# esp8266.net
KiCad netlist of a schematic drawn in EAGLE
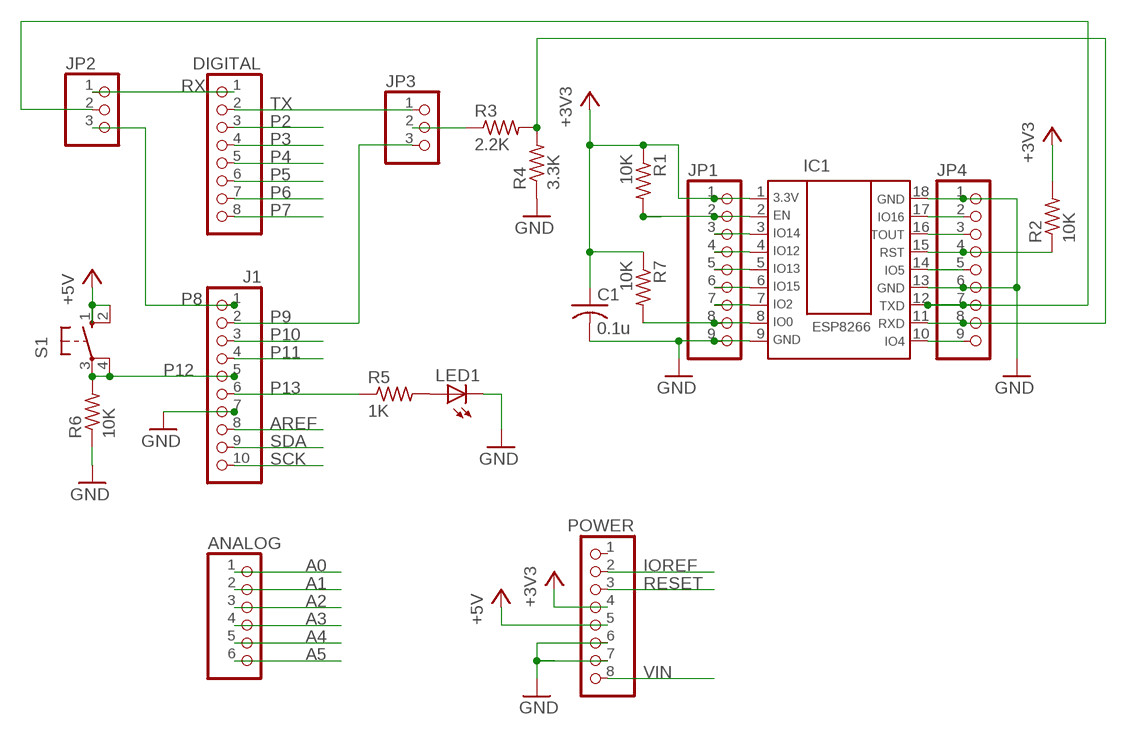
[diagram p0: schematic, sheet 1]

(export (version "E")
  (design (tool "Eeschema 10.0.6"))
  (components
    (comp (ref "ANALOG")
      (value "PINHD-1X6")
      (footprint "eagle-import:1X06")
      (libsource (lib "eagle-import") (part "PINHD-1X6"))
    )
    (comp (ref "C1")
      (value "0.1u")
      (footprint "eagle-import:C050-025X075")
      (libsource (lib "eagle-import") (part "C-US050-025X075"))
    )
    (comp (ref "DIGITAL")
      (value "PINHD-1X8TH")
      (footprint "eagle-import:1X08-TH")
      (libsource (lib "eagle-import") (part "PINHD-1X8TH"))
    )
    (comp (ref "IC1")
      (value "ESP8266")
      (footprint "eagle-import:CEREVO-PKG")
      (libsource (lib "eagle-import") (part "ESP8266"))
    )
    (comp (ref "J1")
      (value "PINHD-1X10TH")
      (footprint "eagle-import:1X10-TH")
      (libsource (lib "eagle-import") (part "PINHD-1X10TH"))
    )
    (comp (ref "JP1")
      (value "PINHD-1X9")
      (footprint "eagle-import:1X09")
      (libsource (lib "eagle-import") (part "PINHD-1X9"))
    )
    (comp (ref "JP2")
      (value "PINHD-1X3")
      (footprint "eagle-import:1X03")
      (libsource (lib "eagle-import") (part "PINHD-1X3"))
    )
    (comp (ref "JP3")
      (value "PINHD-1X3")
      (footprint "eagle-import:1X03")
      (libsource (lib "eagle-import") (part "PINHD-1X3"))
    )
    (comp (ref "JP4")
      (value "PINHD-1X9")
      (footprint "eagle-import:1X09")
      (libsource (lib "eagle-import") (part "PINHD-1X9"))
    )
    (comp (ref "LED1")
      (value "LED3MM")
      (footprint "eagle-import:LED3MM")
      (libsource (lib "eagle-import") (part "LED3MM"))
    )
    (comp (ref "POWER")
      (value "PINHD-1X8TH")
      (footprint "eagle-import:1X08-TH")
      (libsource (lib "eagle-import") (part "PINHD-1X8TH"))
    )
    (comp (ref "R1")
      (value "10K")
      (footprint "eagle-import:0207_10")
      (libsource (lib "eagle-import") (part "R-US_0207/10"))
    )
    (comp (ref "R2")
      (value "10K")
      (footprint "eagle-import:0207_10")
      (libsource (lib "eagle-import") (part "R-US_0207/10"))
    )
    (comp (ref "R3")
      (value "2.2K")
      (footprint "eagle-import:0207_10")
      (libsource (lib "eagle-import") (part "R-US_0207/10"))
    )
    (comp (ref "R4")
      (value "3.3K")
      (footprint "eagle-import:0207_10")
      (libsource (lib "eagle-import") (part "R-US_0207/10"))
    )
    (comp (ref "R5")
      (value "1K")
      (footprint "eagle-import:0207_10")
      (libsource (lib "eagle-import") (part "R-US_0207/10"))
    )
    (comp (ref "R6")
      (value "10K")
      (footprint "eagle-import:0207_10")
      (libsource (lib "eagle-import") (part "R-US_0207/10"))
    )
    (comp (ref "R7")
      (value "10K")
      (footprint "eagle-import:0207_10")
      (libsource (lib "eagle-import") (part "R-US_0207/10"))
    )
    (comp (ref "S1")
      (value "10-XX")
      (footprint "eagle-import:B3F-10XX")
      (fields (field (name "MPN") "B3F-1000"))
      (libsource (lib "eagle-import") (part "10-XX"))
    )
  )
  (nets
    (net (code "1") (name "+3V3") (class "Default")
      (node (ref "C1") (pin "1") (pinfunction "1_1") (pintype "passive"))
      (node (ref "IC1") (pin "1") (pinfunction "1_1") (pintype "passive"))
      (node (ref "JP1") (pin "1") (pinfunction "1_1") (pintype "passive"))
      (node (ref "POWER") (pin "4") (pinfunction "4_4") (pintype "passive"))
      (node (ref "R1") (pin "1") (pinfunction "1_1") (pintype "passive"))
      (node (ref "R2") (pin "2") (pinfunction "2_2") (pintype "passive"))
      (node (ref "R7") (pin "1") (pinfunction "1_1") (pintype "passive"))
    )
    (net (code "2") (name "+5V") (class "Default")
      (node (ref "POWER") (pin "5") (pinfunction "5_5") (pintype "passive"))
      (node (ref "S1") (pin "1") (pinfunction "S_1") (pintype "passive"))
      (node (ref "S1") (pin "2") (pinfunction "S1_2") (pintype "passive"))
    )
    (net (code "3") (name "/A0") (class "Default")
      (node (ref "ANALOG") (pin "1") (pinfunction "1_1") (pintype "passive"))
    )
    (net (code "4") (name "/A1") (class "Default")
      (node (ref "ANALOG") (pin "2") (pinfunction "2_2") (pintype "passive"))
    )
    (net (code "5") (name "/A2") (class "Default")
      (node (ref "ANALOG") (pin "3") (pinfunction "3_3") (pintype "passive"))
    )
    (net (code "6") (name "/A3") (class "Default")
      (node (ref "ANALOG") (pin "4") (pinfunction "4_4") (pintype "passive"))
    )
    (net (code "7") (name "/A4") (class "Default")
      (node (ref "ANALOG") (pin "5") (pinfunction "5_5") (pintype "passive"))
    )
    (net (code "8") (name "/A5") (class "Default")
      (node (ref "ANALOG") (pin "6") (pinfunction "6_6") (pintype "passive"))
    )
    (net (code "9") (name "/AREF") (class "Default")
      (node (ref "J1") (pin "8") (pinfunction "8_8") (pintype "passive"))
    )
    (net (code "10") (name "/IOREF") (class "Default")
      (node (ref "POWER") (pin "2") (pinfunction "2_2") (pintype "passive"))
    )
    (net (code "11") (name "/P2") (class "Default")
      (node (ref "DIGITAL") (pin "3") (pinfunction "3_3") (pintype "passive"))
    )
    (net (code "12") (name "/P3") (class "Default")
      (node (ref "DIGITAL") (pin "4") (pinfunction "4_4") (pintype "passive"))
    )
    (net (code "13") (name "/P4") (class "Default")
      (node (ref "DIGITAL") (pin "5") (pinfunction "5_5") (pintype "passive"))
    )
    (net (code "14") (name "/P5") (class "Default")
      (node (ref "DIGITAL") (pin "6") (pinfunction "6_6") (pintype "passive"))
    )
    (net (code "15") (name "/P6") (class "Default")
      (node (ref "DIGITAL") (pin "7") (pinfunction "7_7") (pintype "passive"))
    )
    (net (code "16") (name "/P7") (class "Default")
      (node (ref "DIGITAL") (pin "8") (pinfunction "8_8") (pintype "passive"))
    )
    (net (code "17") (name "/P8") (class "Default")
      (node (ref "J1") (pin "1") (pinfunction "1_1") (pintype "passive"))
      (node (ref "JP2") (pin "3") (pinfunction "3_3") (pintype "passive"))
    )
    (net (code "18") (name "/P9") (class "Default")
      (node (ref "J1") (pin "2") (pinfunction "2_2") (pintype "passive"))
      (node (ref "JP3") (pin "3") (pinfunction "3_3") (pintype "passive"))
    )
    (net (code "19") (name "/P10") (class "Default")
      (node (ref "J1") (pin "3") (pinfunction "3_3") (pintype "passive"))
    )
    (net (code "20") (name "/P11") (class "Default")
      (node (ref "J1") (pin "4") (pinfunction "4_4") (pintype "passive"))
    )
    (net (code "21") (name "/P12") (class "Default")
      (node (ref "J1") (pin "5") (pinfunction "5_5") (pintype "passive"))
      (node (ref "R6") (pin "2") (pinfunction "2_2") (pintype "passive"))
      (node (ref "S1") (pin "3") (pinfunction "P_3") (pintype "passive"))
      (node (ref "S1") (pin "4") (pinfunction "P1_4") (pintype "passive"))
    )
    (net (code "22") (name "/P13") (class "Default")
      (node (ref "J1") (pin "6") (pinfunction "6_6") (pintype "passive"))
      (node (ref "R5") (pin "1") (pinfunction "1_1") (pintype "passive"))
    )
    (net (code "23") (name "/RESET") (class "Default")
      (node (ref "POWER") (pin "3") (pinfunction "3_3") (pintype "passive"))
    )
    (net (code "24") (name "/RX") (class "Default")
      (node (ref "DIGITAL") (pin "1") (pinfunction "1_1") (pintype "passive"))
      (node (ref "JP2") (pin "1") (pinfunction "1_1") (pintype "passive"))
    )
    (net (code "25") (name "/SCK") (class "Default")
      (node (ref "J1") (pin "10") (pinfunction "10_10") (pintype "passive"))
    )
    (net (code "26") (name "/SDA") (class "Default")
      (node (ref "J1") (pin "9") (pinfunction "9_9") (pintype "passive"))
    )
    (net (code "27") (name "/TX") (class "Default")
      (node (ref "DIGITAL") (pin "2") (pinfunction "2_2") (pintype "passive"))
      (node (ref "JP3") (pin "1") (pinfunction "1_1") (pintype "passive"))
    )
    (net (code "28") (name "/VIN") (class "Default")
      (node (ref "POWER") (pin "8") (pinfunction "8_8") (pintype "passive"))
    )
    (net (code "29") (name "GND") (class "Default")
      (node (ref "C1") (pin "2") (pinfunction "2_2") (pintype "passive"))
      (node (ref "IC1") (pin "13") (pinfunction "13_13") (pintype "passive"))
      (node (ref "IC1") (pin "18") (pinfunction "18_18") (pintype "passive"))
      (node (ref "IC1") (pin "9") (pinfunction "9_9") (pintype "passive"))
      (node (ref "J1") (pin "7") (pinfunction "7_7") (pintype "passive"))
      (node (ref "JP1") (pin "9") (pinfunction "9_9") (pintype "passive"))
      (node (ref "JP4") (pin "1") (pinfunction "1_1") (pintype "passive"))
      (node (ref "JP4") (pin "6") (pinfunction "6_6") (pintype "passive"))
      (node (ref "LED1") (pin "K") (pinfunction "C_K") (pintype "passive"))
      (node (ref "POWER") (pin "6") (pinfunction "6_6") (pintype "passive"))
      (node (ref "POWER") (pin "7") (pinfunction "7_7") (pintype "passive"))
      (node (ref "R4") (pin "1") (pinfunction "1_1") (pintype "passive"))
      (node (ref "R6") (pin "1") (pinfunction "1_1") (pintype "passive"))
    )
    (net (code "30") (name "Net-(IC1-Pad2)") (class "Default")
      (node (ref "IC1") (pin "2") (pinfunction "2_2") (pintype "passive"))
      (node (ref "JP1") (pin "2") (pinfunction "2_2") (pintype "passive"))
      (node (ref "R1") (pin "2") (pinfunction "2_2") (pintype "passive"))
    )
    (net (code "31") (name "Net-(IC1-Pad3)") (class "Default")
      (node (ref "IC1") (pin "3") (pinfunction "3_3") (pintype "passive"))
      (node (ref "JP1") (pin "3") (pinfunction "3_3") (pintype "passive"))
    )
    (net (code "32") (name "Net-(IC1-Pad4)") (class "Default")
      (node (ref "IC1") (pin "4") (pinfunction "4_4") (pintype "passive"))
      (node (ref "JP1") (pin "4") (pinfunction "4_4") (pintype "passive"))
    )
    (net (code "33") (name "Net-(IC1-Pad5)") (class "Default")
      (node (ref "IC1") (pin "5") (pinfunction "5_5") (pintype "passive"))
      (node (ref "JP1") (pin "5") (pinfunction "5_5") (pintype "passive"))
    )
    (net (code "34") (name "Net-(IC1-Pad6)") (class "Default")
      (node (ref "IC1") (pin "6") (pinfunction "6_6") (pintype "passive"))
      (node (ref "JP1") (pin "6") (pinfunction "6_6") (pintype "passive"))
    )
    (net (code "35") (name "Net-(IC1-Pad7)") (class "Default")
      (node (ref "IC1") (pin "7") (pinfunction "7_7") (pintype "passive"))
      (node (ref "JP1") (pin "7") (pinfunction "7_7") (pintype "passive"))
    )
    (net (code "36") (name "Net-(IC1-Pad8)") (class "Default")
      (node (ref "IC1") (pin "8") (pinfunction "8_8") (pintype "passive"))
      (node (ref "JP1") (pin "8") (pinfunction "8_8") (pintype "passive"))
      (node (ref "R7") (pin "2") (pinfunction "2_2") (pintype "passive"))
    )
    (net (code "37") (name "Net-(IC1-Pad10)") (class "Default")
      (node (ref "IC1") (pin "10") (pinfunction "10_10") (pintype "passive"))
      (node (ref "JP4") (pin "9") (pinfunction "9_9") (pintype "passive"))
    )
    (net (code "38") (name "Net-(IC1-Pad11)") (class "Default")
      (node (ref "IC1") (pin "11") (pinfunction "11_11") (pintype "passive"))
      (node (ref "JP4") (pin "8") (pinfunction "8_8") (pintype "passive"))
      (node (ref "R3") (pin "2") (pinfunction "2_2") (pintype "passive"))
      (node (ref "R4") (pin "2") (pinfunction "2_2") (pintype "passive"))
    )
    (net (code "39") (name "Net-(IC1-Pad12)") (class "Default")
      (node (ref "IC1") (pin "12") (pinfunction "12_12") (pintype "passive"))
      (node (ref "JP2") (pin "2") (pinfunction "2_2") (pintype "passive"))
      (node (ref "JP4") (pin "7") (pinfunction "7_7") (pintype "passive"))
    )
    (net (code "40") (name "Net-(IC1-Pad14)") (class "Default")
      (node (ref "IC1") (pin "14") (pinfunction "14_14") (pintype "passive"))
      (node (ref "JP4") (pin "5") (pinfunction "5_5") (pintype "passive"))
    )
    (net (code "41") (name "Net-(IC1-Pad15)") (class "Default")
      (node (ref "IC1") (pin "15") (pinfunction "15_15") (pintype "passive"))
      (node (ref "JP4") (pin "4") (pinfunction "4_4") (pintype "passive"))
      (node (ref "R2") (pin "1") (pinfunction "1_1") (pintype "passive"))
    )
    (net (code "42") (name "Net-(IC1-Pad16)") (class "Default")
      (node (ref "IC1") (pin "16") (pinfunction "16_16") (pintype "passive"))
      (node (ref "JP4") (pin "3") (pinfunction "3_3") (pintype "passive"))
    )
    (net (code "43") (name "Net-(IC1-Pad17)") (class "Default")
      (node (ref "IC1") (pin "17") (pinfunction "17_17") (pintype "passive"))
      (node (ref "JP4") (pin "2") (pinfunction "2_2") (pintype "passive"))
    )
    (net (code "44") (name "Net-(JP3-Pad2)") (class "Default")
      (node (ref "JP3") (pin "2") (pinfunction "2_2") (pintype "passive"))
      (node (ref "R3") (pin "1") (pinfunction "1_1") (pintype "passive"))
    )
    (net (code "45") (name "Net-(LED1-PadA)") (class "Default")
      (node (ref "LED1") (pin "A") (pinfunction "A_A") (pintype "passive"))
      (node (ref "R5") (pin "2") (pinfunction "2_2") (pintype "passive"))
    )
    (net (code "46") (name "unconnected-(POWER-Pad1)") (class "Default")
      (node (ref "POWER") (pin "1") (pinfunction "1_1") (pintype "passive"))
    )
  )
)
